# Schematic.net
KiCad netlist of a schematic drawn in EAGLE
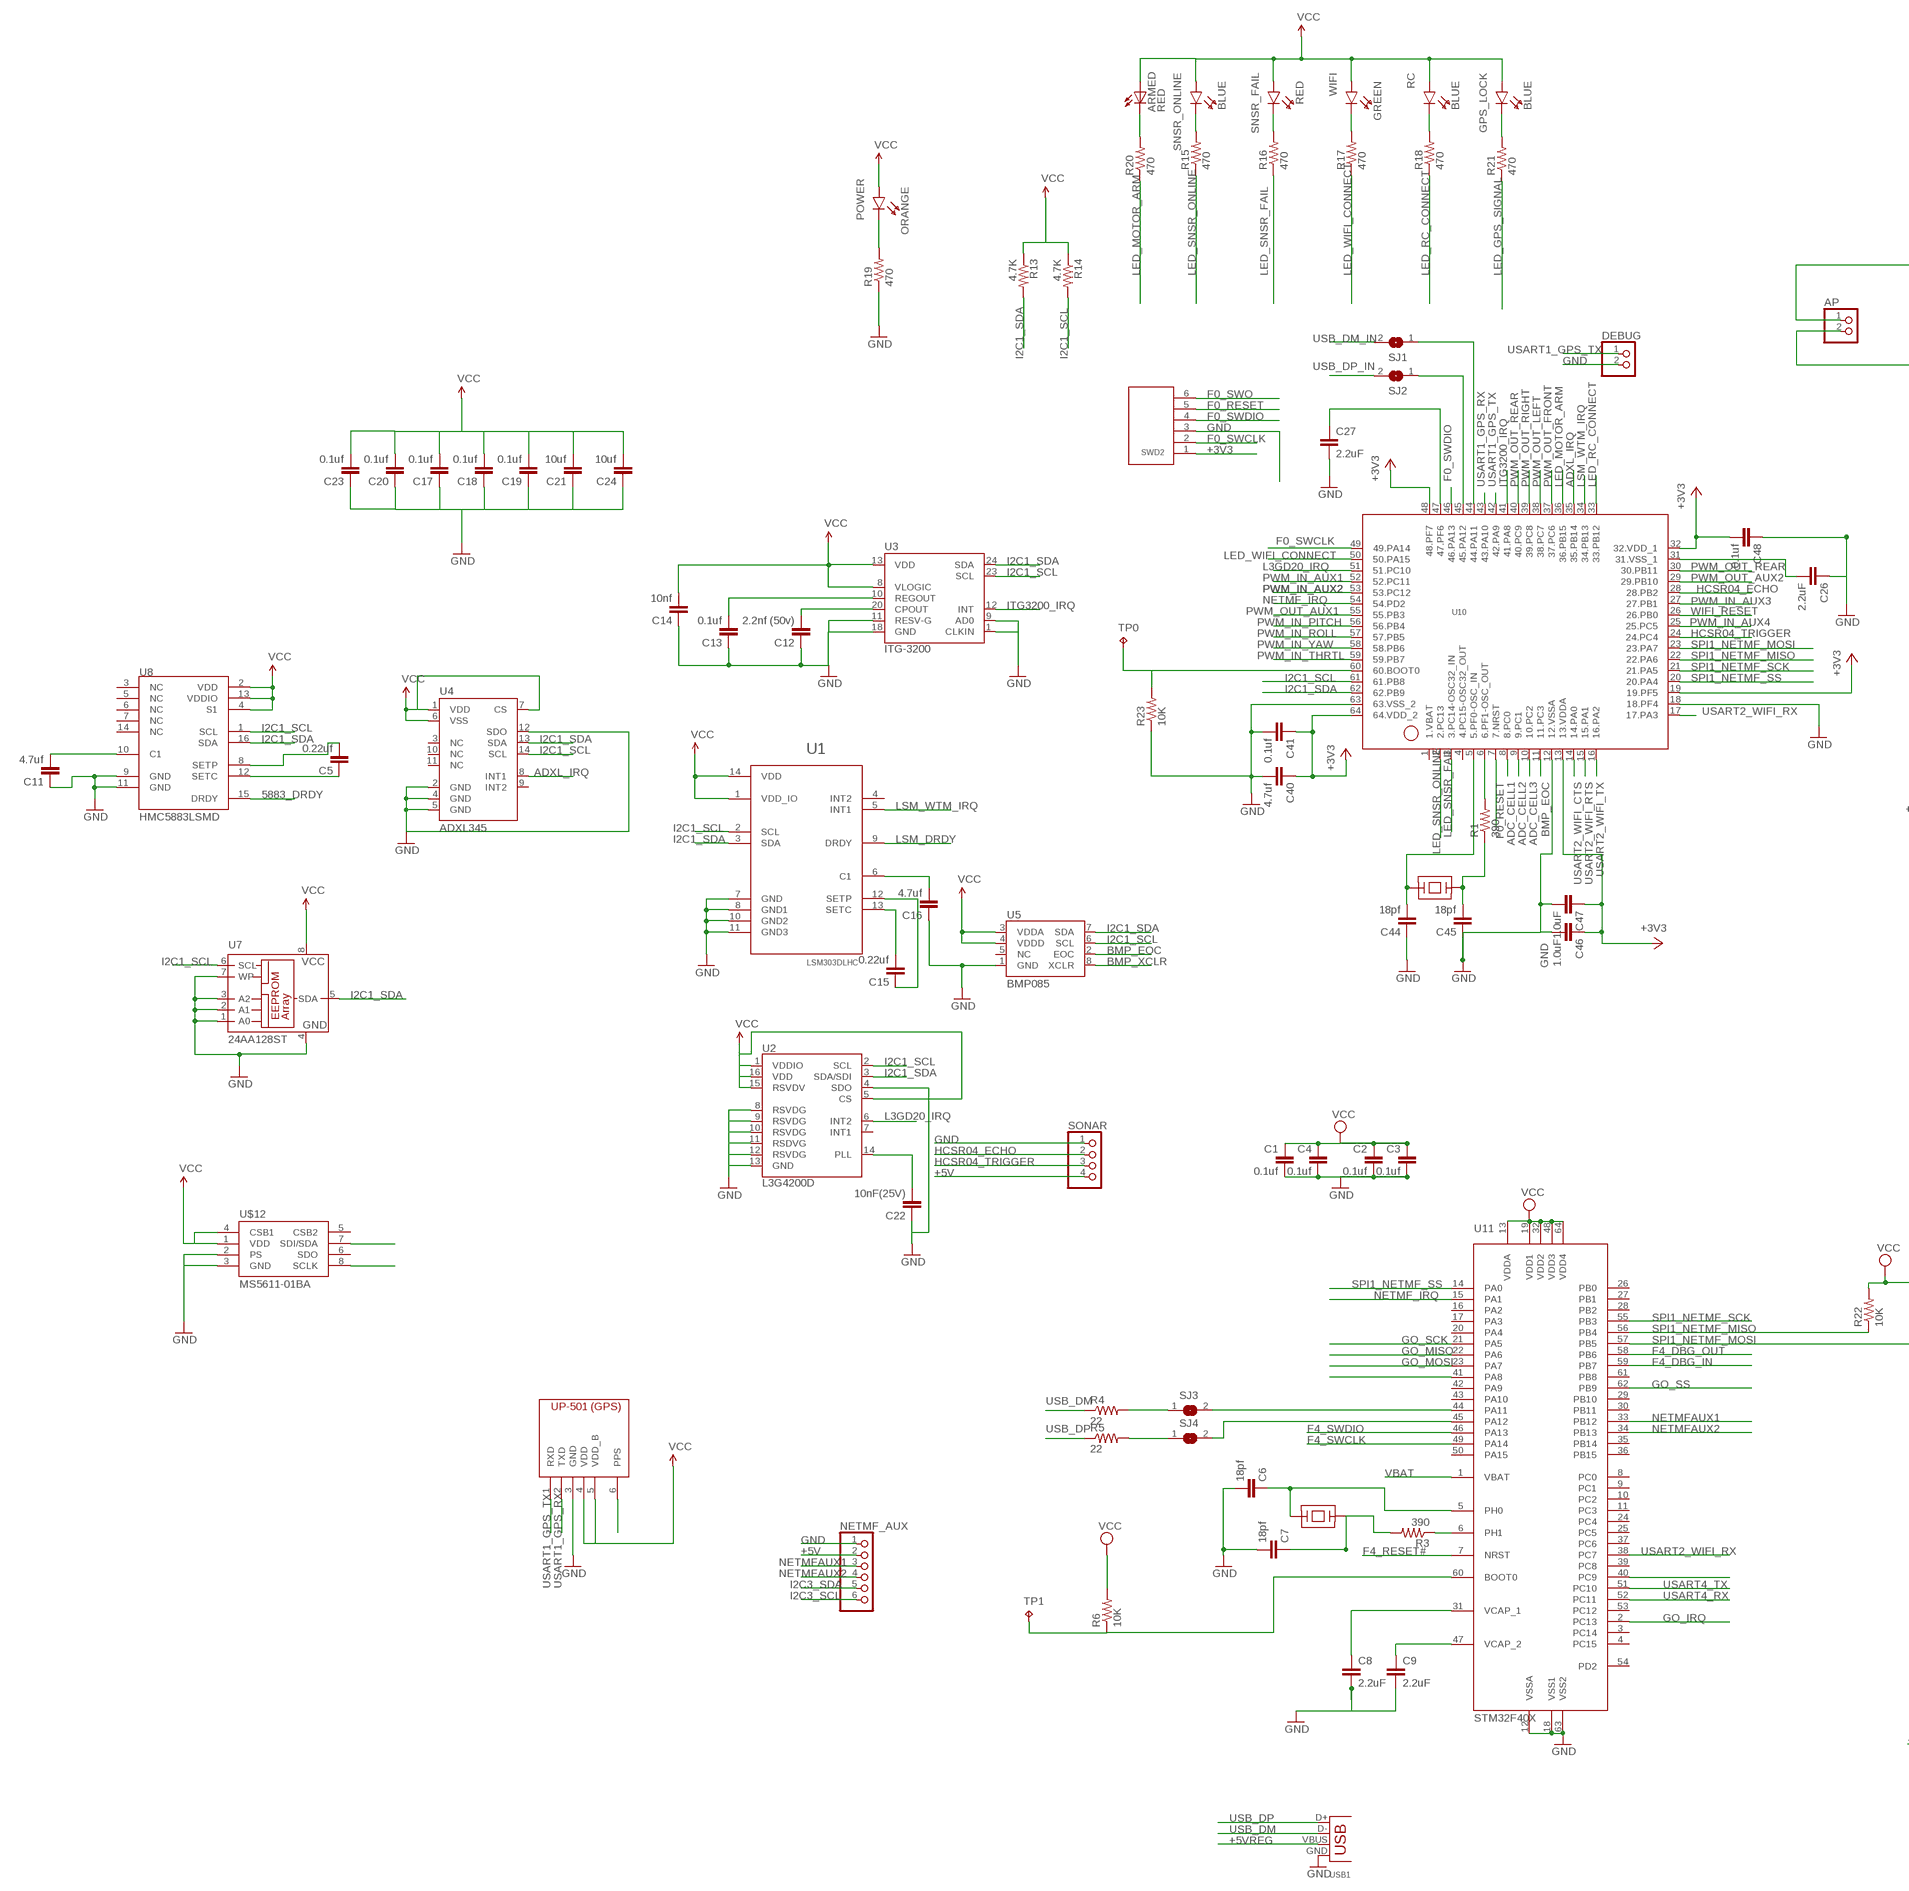
[diagram p0: schematic, sheet 1, part 1 of 2]
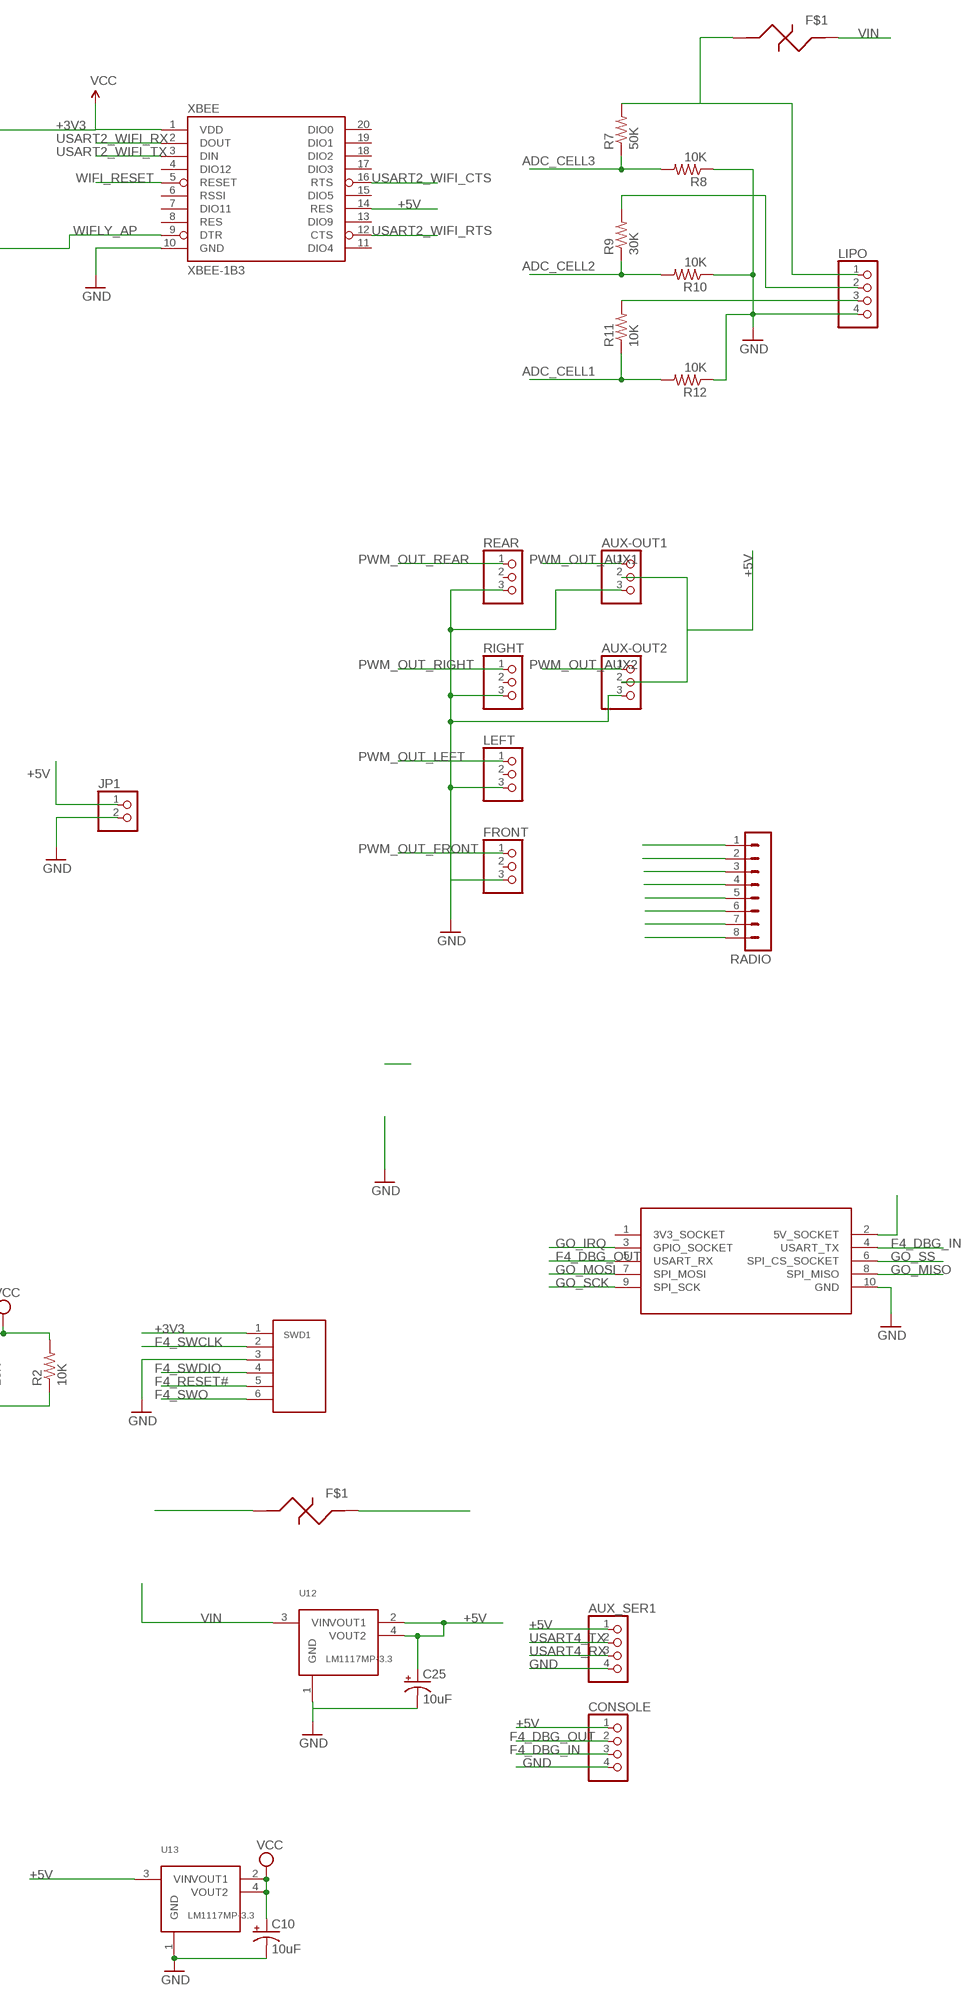
[diagram p1: schematic, sheet 1, part 2 of 2]

(export (version "E")
  (design (tool "Eeschema 10.0.6"))
  (components
    (comp (ref "AP")
      (value "PINHD-1X2")
      (footprint "eagle-import:1X02")
      (libsource (lib "eagle-import") (part "PINHD-1X2"))
    )
    (comp (ref "ARMED")
      (value "RED")
      (footprint "eagle-import:LED-1206")
      (libsource (lib "eagle-import") (part "LED-REDLILYPAD"))
    )
    (comp (ref "AUX-OUT1")
      (value "PINHD-1X3")
      (footprint "eagle-import:1X03")
      (libsource (lib "eagle-import") (part "PINHD-1X3"))
    )
    (comp (ref "AUX-OUT2")
      (value "PINHD-1X3")
      (footprint "eagle-import:1X03")
      (libsource (lib "eagle-import") (part "PINHD-1X3"))
    )
    (comp (ref "AUX_SER1")
      (value "PINHD-1X4")
      (footprint "eagle-import:1X04")
      (libsource (lib "eagle-import") (part "PINHD-1X4"))
    )
    (comp (ref "C1")
      (value "0.1uf")
      (footprint "eagle-import:0805")
      (libsource (lib "eagle-import") (part "SparkFun-Passives_CAP0805"))
    )
    (comp (ref "C2")
      (value "0.1uf")
      (footprint "eagle-import:0805")
      (libsource (lib "eagle-import") (part "SparkFun-Passives_CAP0805"))
    )
    (comp (ref "C3")
      (value "0.1uf")
      (footprint "eagle-import:0805")
      (libsource (lib "eagle-import") (part "SparkFun-Passives_CAP0805"))
    )
    (comp (ref "C4")
      (value "0.1uf")
      (footprint "eagle-import:0805")
      (libsource (lib "eagle-import") (part "SparkFun-Passives_CAP0805"))
    )
    (comp (ref "C5")
      (value "0.22uf")
      (footprint "eagle-import:0805")
      (libsource (lib "eagle-import") (part "CAP0805"))
    )
    (comp (ref "C6")
      (value "18pf")
      (footprint "eagle-import:0805")
      (libsource (lib "eagle-import") (part "SparkFun-Passives_CAP0805"))
    )
    (comp (ref "C7")
      (value "18pf")
      (footprint "eagle-import:0805")
      (libsource (lib "eagle-import") (part "SparkFun-Passives_CAP0805"))
    )
    (comp (ref "C8")
      (value "2.2uF")
      (footprint "eagle-import:0805")
      (libsource (lib "eagle-import") (part "SparkFun-Passives_CAP0805"))
    )
    (comp (ref "C9")
      (value "2.2uF")
      (footprint "eagle-import:0805")
      (libsource (lib "eagle-import") (part "SparkFun-Passives_CAP0805"))
    )
    (comp (ref "C10")
      (value "10uF")
      (footprint "eagle-import:CT3528")
      (libsource (lib "eagle-import") (part "CPOL-USCT3528"))
    )
    (comp (ref "C11")
      (value "4.7uf")
      (footprint "eagle-import:0805")
      (libsource (lib "eagle-import") (part "CAP0805"))
    )
    (comp (ref "C12")
      (value "2.2nf (50v)")
      (footprint "eagle-import:0805")
      (libsource (lib "eagle-import") (part "CAP0805"))
    )
    (comp (ref "C13")
      (value "0.1uf")
      (footprint "eagle-import:0805")
      (libsource (lib "eagle-import") (part "CAP0805"))
    )
    (comp (ref "C14")
      (value "10nf")
      (footprint "eagle-import:0805")
      (libsource (lib "eagle-import") (part "CAP0805"))
    )
    (comp (ref "C15")
      (value "0.22uf")
      (footprint "eagle-import:0805")
      (libsource (lib "eagle-import") (part "CAP0805"))
    )
    (comp (ref "C16")
      (value "4.7uf")
      (footprint "eagle-import:0805")
      (libsource (lib "eagle-import") (part "CAP0805"))
    )
    (comp (ref "C17")
      (value "0.1uf")
      (footprint "eagle-import:0805")
      (libsource (lib "eagle-import") (part "CAP0805"))
    )
    (comp (ref "C18")
      (value "0.1uf")
      (footprint "eagle-import:0805")
      (libsource (lib "eagle-import") (part "CAP0805"))
    )
    (comp (ref "C19")
      (value "0.1uf")
      (footprint "eagle-import:0805")
      (libsource (lib "eagle-import") (part "CAP0805"))
    )
    (comp (ref "C20")
      (value "0.1uf")
      (footprint "eagle-import:0805")
      (libsource (lib "eagle-import") (part "CAP0805"))
    )
    (comp (ref "C21")
      (value "10uf")
      (footprint "eagle-import:0805")
      (libsource (lib "eagle-import") (part "CAP0805"))
    )
    (comp (ref "C22")
      (value "10nF(25V)")
      (footprint "eagle-import:0805")
      (libsource (lib "eagle-import") (part "CAP0805"))
    )
    (comp (ref "C23")
      (value "0.1uf")
      (footprint "eagle-import:0805")
      (libsource (lib "eagle-import") (part "CAP0805"))
    )
    (comp (ref "C24")
      (value "10uf")
      (footprint "eagle-import:0805")
      (libsource (lib "eagle-import") (part "CAP0805"))
    )
    (comp (ref "C25")
      (value "10uF")
      (footprint "eagle-import:CT3528")
      (libsource (lib "eagle-import") (part "CPOL-USCT3528"))
    )
    (comp (ref "C26")
      (value "2.2uF")
      (footprint "eagle-import:0805")
      (libsource (lib "eagle-import") (part "SparkFun-Passives_CAP0805"))
    )
    (comp (ref "C27")
      (value "2.2uF")
      (footprint "eagle-import:0805")
      (libsource (lib "eagle-import") (part "SparkFun-Passives_CAP0805"))
    )
    (comp (ref "C40")
      (value "4.7uf")
      (footprint "eagle-import:0805")
      (libsource (lib "eagle-import") (part "SparkFun-Passives_CAP0805"))
    )
    (comp (ref "C41")
      (value "0.1uf")
      (footprint "eagle-import:0805")
      (libsource (lib "eagle-import") (part "SparkFun-Passives_CAP0805"))
    )
    (comp (ref "C44")
      (value "18pf")
      (footprint "eagle-import:0805")
      (libsource (lib "eagle-import") (part "SparkFun-Passives_CAP0805"))
    )
    (comp (ref "C45")
      (value "18pf")
      (footprint "eagle-import:0805")
      (libsource (lib "eagle-import") (part "SparkFun-Passives_CAP0805"))
    )
    (comp (ref "C46")
      (value "1.0uF")
      (footprint "eagle-import:0805")
      (libsource (lib "eagle-import") (part "SparkFun-Passives_CAP0805"))
    )
    (comp (ref "C47")
      (value "1.0uF")
      (footprint "eagle-import:0805")
      (libsource (lib "eagle-import") (part "SparkFun-Passives_CAP0805"))
    )
    (comp (ref "C48")
      (value "0.1uf")
      (footprint "eagle-import:0805")
      (libsource (lib "eagle-import") (part "SparkFun-Passives_CAP0805"))
    )
    (comp (ref "CONSOLE")
      (value "PINHD-1X4")
      (footprint "eagle-import:1X04")
      (libsource (lib "eagle-import") (part "PINHD-1X4"))
    )
    (comp (ref "DEBUG")
      (value "PINHD-1X2")
      (footprint "eagle-import:1X02")
      (libsource (lib "eagle-import") (part "PINHD-1X2"))
    )
    (comp (ref "F1")
      (value "1206L050_FUSE")
      (footprint "eagle-import:1206L050_FUSE")
      (libsource (lib "eagle-import") (part "1206L050_FUSE"))
    )
    (comp (ref "F2")
      (value "1206L050_FUSE")
      (footprint "eagle-import:1206L050_FUSE")
      (libsource (lib "eagle-import") (part "1206L050_FUSE"))
    )
    (comp (ref "FRONT")
      (value "PINHD-1X3")
      (footprint "eagle-import:1X03")
      (libsource (lib "eagle-import") (part "PINHD-1X3"))
    )
    (comp (ref "GO_BUS")
      (value "GO!BUS")
      (footprint "eagle-import:PIN2ROW_0.05_")
      (libsource (lib "eagle-import") (part "GO!BUS"))
    )
    (comp (ref "GPS_LOCK")
      (value "BLUE")
      (footprint "eagle-import:LED0805")
      (libsource (lib "eagle-import") (part "SMD_LED0805"))
    )
    (comp (ref "JP1")
      (value "PINHD-1X2")
      (footprint "eagle-import:1X02")
      (libsource (lib "eagle-import") (part "PINHD-1X2"))
    )
    (comp (ref "LEFT")
      (value "PINHD-1X3")
      (footprint "eagle-import:1X03")
      (libsource (lib "eagle-import") (part "PINHD-1X3"))
    )
    (comp (ref "LIPO")
      (value "PINHD-1X4")
      (footprint "eagle-import:1X04")
      (libsource (lib "eagle-import") (part "PINHD-1X4"))
    )
    (comp (ref "NETMF_AUX")
      (value "PINHD-1X6")
      (footprint "eagle-import:1X06")
      (libsource (lib "eagle-import") (part "PINHD-1X6"))
    )
    (comp (ref "POWER")
      (value "ORANGE")
      (footprint "eagle-import:LED0805")
      (libsource (lib "eagle-import") (part "SMD_LED0805"))
    )
    (comp (ref "R1")
      (value "390")
      (footprint "eagle-import:0805")
      (libsource (lib "eagle-import") (part "RESISTOR0805-RES"))
    )
    (comp (ref "R2")
      (value "10K")
      (footprint "eagle-import:0805")
      (libsource (lib "eagle-import") (part "RESISTOR0805-RES"))
    )
    (comp (ref "R3")
      (value "390")
      (footprint "eagle-import:0805")
      (libsource (lib "eagle-import") (part "RESISTOR0805-RES"))
    )
    (comp (ref "R4")
      (value "22")
      (footprint "eagle-import:0805")
      (libsource (lib "eagle-import") (part "RESISTOR0805-RES"))
    )
    (comp (ref "R5")
      (value "22")
      (footprint "eagle-import:0805")
      (libsource (lib "eagle-import") (part "RESISTOR0805-RES"))
    )
    (comp (ref "R6")
      (value "10K")
      (footprint "eagle-import:0805")
      (libsource (lib "eagle-import") (part "RESISTOR0805-RES"))
    )
    (comp (ref "R7")
      (value "50K")
      (footprint "eagle-import:0805")
      (libsource (lib "eagle-import") (part "RESISTOR0805-RES"))
    )
    (comp (ref "R8")
      (value "10K")
      (footprint "eagle-import:0805")
      (libsource (lib "eagle-import") (part "RESISTOR0805-RES"))
    )
    (comp (ref "R9")
      (value "30K")
      (footprint "eagle-import:0805")
      (libsource (lib "eagle-import") (part "RESISTOR0805-RES"))
    )
    (comp (ref "R10")
      (value "10K")
      (footprint "eagle-import:0805")
      (libsource (lib "eagle-import") (part "RESISTOR0805-RES"))
    )
    (comp (ref "R11")
      (value "10K")
      (footprint "eagle-import:0805")
      (libsource (lib "eagle-import") (part "RESISTOR0805-RES"))
    )
    (comp (ref "R12")
      (value "10K")
      (footprint "eagle-import:0805")
      (libsource (lib "eagle-import") (part "RESISTOR0805-RES"))
    )
    (comp (ref "R13")
      (value "4.7K")
      (footprint "eagle-import:0805")
      (libsource (lib "eagle-import") (part "RESISTOR0805-RES"))
    )
    (comp (ref "R14")
      (value "4.7K")
      (footprint "eagle-import:0805")
      (libsource (lib "eagle-import") (part "RESISTOR0805-RES"))
    )
    (comp (ref "R15")
      (value "470")
      (footprint "eagle-import:0805")
      (libsource (lib "eagle-import") (part "RESISTOR0805-RES"))
    )
    (comp (ref "R16")
      (value "470")
      (footprint "eagle-import:0805")
      (libsource (lib "eagle-import") (part "RESISTOR0805-RES"))
    )
    (comp (ref "R17")
      (value "470")
      (footprint "eagle-import:0805")
      (libsource (lib "eagle-import") (part "RESISTOR0805-RES"))
    )
    (comp (ref "R18")
      (value "470")
      (footprint "eagle-import:0805")
      (libsource (lib "eagle-import") (part "RESISTOR0805-RES"))
    )
    (comp (ref "R19")
      (value "470")
      (footprint "eagle-import:0805")
      (libsource (lib "eagle-import") (part "RESISTOR0805-RES"))
    )
    (comp (ref "R20")
      (value "470")
      (footprint "eagle-import:0805")
      (libsource (lib "eagle-import") (part "RESISTOR0805-RES"))
    )
    (comp (ref "R21")
      (value "470")
      (footprint "eagle-import:0805")
      (libsource (lib "eagle-import") (part "RESISTOR0805-RES"))
    )
    (comp (ref "R22")
      (value "10K")
      (footprint "eagle-import:0805")
      (libsource (lib "eagle-import") (part "RESISTOR0805-RES"))
    )
    (comp (ref "R23")
      (value "10K")
      (footprint "eagle-import:0805")
      (libsource (lib "eagle-import") (part "RESISTOR0805-RES"))
    )
    (comp (ref "RADIO")
      (value "MA08-1")
      (footprint "eagle-import:MA08-1")
      (libsource (lib "eagle-import") (part "MA08-1"))
    )
    (comp (ref "RC")
      (value "BLUE")
      (footprint "eagle-import:LED0805")
      (libsource (lib "eagle-import") (part "SMD_LED0805"))
    )
    (comp (ref "REAR")
      (value "PINHD-1X3")
      (footprint "eagle-import:1X03")
      (libsource (lib "eagle-import") (part "PINHD-1X3"))
    )
    (comp (ref "RIGHT")
      (value "PINHD-1X3")
      (footprint "eagle-import:1X03")
      (libsource (lib "eagle-import") (part "PINHD-1X3"))
    )
    (comp (ref "SJ1") (value "SJ") (footprint "eagle-import:SJ") (libsource (lib "eagle-import") (part "SJ")))
    (comp (ref "SJ2") (value "SJ") (footprint "eagle-import:SJ") (libsource (lib "eagle-import") (part "SJ")))
    (comp (ref "SJ3") (value "SJ") (footprint "eagle-import:SJ") (libsource (lib "eagle-import") (part "SJ")))
    (comp (ref "SJ4") (value "SJ") (footprint "eagle-import:SJ") (libsource (lib "eagle-import") (part "SJ")))
    (comp (ref "SNSR_FAIL")
      (value "RED")
      (footprint "eagle-import:LED0805")
      (libsource (lib "eagle-import") (part "SMD_LED0805"))
    )
    (comp (ref "SNSR_ONLINE")
      (value "BLUE")
      (footprint "eagle-import:LED0805")
      (libsource (lib "eagle-import") (part "SMD_LED0805"))
    )
    (comp (ref "SONAR")
      (value "PINHD-1X4")
      (footprint "eagle-import:1X04")
      (libsource (lib "eagle-import") (part "PINHD-1X4"))
    )
    (comp (ref "SWD1")
      (value "JST-6PIN")
      (footprint "eagle-import:JSTX6")
      (libsource (lib "eagle-import") (part "JST-6PIN"))
    )
    (comp (ref "SWD2")
      (value "SWD-STM32F0")
      (footprint "eagle-import:JSTX6")
      (libsource (lib "eagle-import") (part "JST-6PIN"))
    )
    (comp (ref "TP0")
      (value "TPTP15R")
      (footprint "eagle-import:TP15R")
      (libsource (lib "eagle-import") (part "TPTP15R"))
    )
    (comp (ref "TP1")
      (value "TPTP15R")
      (footprint "eagle-import:TP15R")
      (libsource (lib "eagle-import") (part "TPTP15R"))
    )
    (comp (ref "U$4")
      (value "UP501")
      (footprint "eagle-import:UP-501")
      (libsource (lib "eagle-import") (part "UP501"))
    )
    (comp (ref "U$12")
      (value "MS5611-01BA")
      (footprint "eagle-import:MS5611-01BA")
      (libsource (lib "eagle-import") (part "MS5611-01BA"))
    )
    (comp (ref "U1")
      (value "LSM303DLHC")
      (footprint "eagle-import:LGA3X5X1-14L")
      (libsource (lib "eagle-import") (part "LSM303DLHC"))
    )
    (comp (ref "U2")
      (value "L3G4200D")
      (footprint "eagle-import:LGA16-4X4")
      (libsource (lib "eagle-import") (part "L3G4200D"))
    )
    (comp (ref "U3")
      (value "ITG-3200")
      (footprint "eagle-import:QFN-24")
      (libsource (lib "eagle-import") (part "ITG-3200"))
    )
    (comp (ref "U4")
      (value "ADXL345")
      (footprint "eagle-import:LGA14")
      (libsource (lib "eagle-import") (part "ADXL345"))
    )
    (comp (ref "U5")
      (value "BMP085")
      (footprint "eagle-import:BMP085")
      (libsource (lib "eagle-import") (part "BMP085"))
    )
    (comp (ref "U7")
      (value "24AA128ST")
      (footprint "eagle-import:TSSOP8")
      (fields
        (field (name "MF") "MICROCHIP")
        (field (name "MPN") "24AA128-I/ST")
        (field (name "MPN_1") "24AA128-I/ST")
        (field (name "OC_FARNELL") "unknown")
        (field (name "OC_NEWARK") "92C6843")
      )
      (libsource (lib "eagle-import") (part "24STAA128"))
    )
    (comp (ref "U8")
      (value "HMC5883LSMD")
      (footprint "eagle-import:16LPCC")
      (libsource (lib "eagle-import") (part "HMC5883LSMD"))
    )
    (comp (ref "U10")
      (value "STM32F051XXX")
      (footprint "eagle-import:STM32F051XXX_LPFP64")
      (libsource (lib "eagle-import") (part "STM32F051XXX"))
    )
    (comp (ref "U11")
      (value "STM32F40X")
      (footprint "eagle-import:LQFP64")
      (libsource (lib "eagle-import") (part "STM32F40X"))
    )
    (comp (ref "U12")
      (value "LM1117MP-3.3")
      (footprint "eagle-import:SOT223")
      (libsource (lib "eagle-import") (part "LM1117"))
    )
    (comp (ref "U13")
      (value "LM1117MP-3.3")
      (footprint "eagle-import:SOT223")
      (libsource (lib "eagle-import") (part "LM1117"))
    )
    (comp (ref "USB1")
      (value "DX2R005HN2E700")
      (footprint "eagle-import:USB-MB-S")
      (libsource (lib "eagle-import") (part "USB-MB-S"))
    )
    (comp (ref "WIFI")
      (value "GREEN")
      (footprint "eagle-import:LED0805")
      (libsource (lib "eagle-import") (part "SMD_LED0805"))
    )
    (comp (ref "X1")
      (value "ABRACON_ABM7")
      (footprint "eagle-import:ABRACON_ABM7_CERAMIC_XTAL")
      (libsource (lib "eagle-import") (part "ABRACON_ABM7"))
    )
    (comp (ref "X2")
      (value "ABRACON_ABM7")
      (footprint "eagle-import:ABRACON_ABM7_CERAMIC_XTAL")
      (libsource (lib "eagle-import") (part "ABRACON_ABM7"))
    )
    (comp (ref "XBEE")
      (value "XBEE-1B3")
      (footprint "eagle-import:XBEE-SMD")
      (libsource (lib "eagle-import") (part "XBEE-1B3"))
    )
  )
  (nets
    (net (code "1") (name "+3V3") (class "Default")
      (node (ref "AP") (pin "1") (pinfunction "1_1") (pintype "passive"))
      (node (ref "ARMED") (pin "A") (pinfunction "A_A") (pintype "passive"))
      (node (ref "C1") (pin "1") (pinfunction "1_1") (pintype "passive"))
      (node (ref "C10") (pin "+") (pinfunction "+_+") (pintype "passive"))
      (node (ref "C14") (pin "2") (pinfunction "2_2") (pintype "passive"))
      (node (ref "C17") (pin "2") (pinfunction "2_2") (pintype "passive"))
      (node (ref "C18") (pin "2") (pinfunction "2_2") (pintype "passive"))
      (node (ref "C19") (pin "2") (pinfunction "2_2") (pintype "passive"))
      (node (ref "C2") (pin "1") (pinfunction "1_1") (pintype "passive"))
      (node (ref "C20") (pin "2") (pinfunction "2_2") (pintype "passive"))
      (node (ref "C21") (pin "2") (pinfunction "2_2") (pintype "passive"))
      (node (ref "C23") (pin "2") (pinfunction "2_2") (pintype "passive"))
      (node (ref "C24") (pin "2") (pinfunction "2_2") (pintype "passive"))
      (node (ref "C3") (pin "1") (pinfunction "1_1") (pintype "passive"))
      (node (ref "C4") (pin "1") (pinfunction "1_1") (pintype "passive"))
      (node (ref "C40") (pin "1") (pinfunction "1_1") (pintype "passive"))
      (node (ref "C41") (pin "1") (pinfunction "1_1") (pintype "passive"))
      (node (ref "C46") (pin "1") (pinfunction "1_1") (pintype "passive"))
      (node (ref "C47") (pin "1") (pinfunction "1_1") (pintype "passive"))
      (node (ref "C48") (pin "2") (pinfunction "2_2") (pintype "passive"))
      (node (ref "GPS_LOCK") (pin "P$1") (pinfunction "A_P$1") (pintype "passive"))
      (node (ref "POWER") (pin "P$1") (pinfunction "A_P$1") (pintype "passive"))
      (node (ref "R13") (pin "1") (pinfunction "1_1") (pintype "passive"))
      (node (ref "R14") (pin "1") (pinfunction "1_1") (pintype "passive"))
      (node (ref "R2") (pin "2") (pinfunction "2_2") (pintype "passive"))
      (node (ref "R22") (pin "2") (pinfunction "2_2") (pintype "passive"))
      (node (ref "R6") (pin "2") (pinfunction "2_2") (pintype "passive"))
      (node (ref "RC") (pin "P$1") (pinfunction "A_P$1") (pintype "passive"))
      (node (ref "SNSR_FAIL") (pin "P$1") (pinfunction "A_P$1") (pintype "passive"))
      (node (ref "SNSR_ONLINE") (pin "P$1") (pinfunction "A_P$1") (pintype "passive"))
      (node (ref "SWD1") (pin "1") (pinfunction "P$1_1") (pintype "bidirectional"))
      (node (ref "SWD2") (pin "1") (pinfunction "P$1_1") (pintype "bidirectional"))
      (node (ref "U$12") (pin "1") (pinfunction "VDD_1") (pintype "bidirectional"))
      (node (ref "U$12") (pin "4") (pinfunction "CSB1_4") (pintype "bidirectional"))
      (node (ref "U$4") (pin "4") (pinfunction "VDD_4") (pintype "bidirectional"))
      (node (ref "U$4") (pin "5") (pinfunction "VDD_B_5") (pintype "bidirectional"))
      (node (ref "U1") (pin "1") (pinfunction "VDD_IO_1") (pintype "power_in"))
      (node (ref "U1") (pin "14") (pinfunction "VDD_14") (pintype "power_in"))
      (node (ref "U10") (pin "13") (pinfunction "13.VDDA_13") (pintype "power_in"))
      (node (ref "U10") (pin "19") (pinfunction "19.PF5_19") (pintype "bidirectional"))
      (node (ref "U10") (pin "32") (pinfunction "32.VDD_1_32") (pintype "power_in"))
      (node (ref "U10") (pin "48") (pinfunction "48.PF7_48") (pintype "power_in"))
      (node (ref "U10") (pin "64") (pinfunction "64.VDD_2_64") (pintype "power_in"))
      (node (ref "U11") (pin "13") (pinfunction "VDDA_13") (pintype "bidirectional"))
      (node (ref "U11") (pin "19") (pinfunction "VDD1_19") (pintype "bidirectional"))
      (node (ref "U11") (pin "32") (pinfunction "VDD2_32") (pintype "bidirectional"))
      (node (ref "U11") (pin "48") (pinfunction "VDD3_48") (pintype "bidirectional"))
      (node (ref "U11") (pin "64") (pinfunction "VDD4_64") (pintype "bidirectional"))
      (node (ref "U13") (pin "2") (pinfunction "VOUT1_2") (pintype "bidirectional"))
      (node (ref "U13") (pin "4") (pinfunction "VOUT2_4") (pintype "bidirectional"))
      (node (ref "U2") (pin "1") (pinfunction "VDDIO_1") (pintype "bidirectional"))
      (node (ref "U2") (pin "15") (pinfunction "RSVDV_15") (pintype "bidirectional"))
      (node (ref "U2") (pin "16") (pinfunction "VDD_16") (pintype "bidirectional"))
      (node (ref "U2") (pin "5") (pinfunction "CS_5") (pintype "bidirectional"))
      (node (ref "U3") (pin "13") (pinfunction "VDD_13") (pintype "bidirectional"))
      (node (ref "U3") (pin "8") (pinfunction "VLOGIC_8") (pintype "bidirectional"))
      (node (ref "U4") (pin "1") (pinfunction "VDD_1") (pintype "bidirectional"))
      (node (ref "U4") (pin "6") (pinfunction "VSS_6") (pintype "bidirectional"))
      (node (ref "U4") (pin "7") (pinfunction "CS_7") (pintype "bidirectional"))
      (node (ref "U5") (pin "3") (pinfunction "VDDA_3") (pintype "power_in"))
      (node (ref "U5") (pin "4") (pinfunction "VDDD_4") (pintype "power_in"))
      (node (ref "U7") (pin "8") (pinfunction "VCC_8") (pintype "power_in"))
      (node (ref "U8") (pin "13") (pinfunction "VDDIO_13") (pintype "bidirectional"))
      (node (ref "U8") (pin "2") (pinfunction "VDD_2") (pintype "bidirectional"))
      (node (ref "U8") (pin "4") (pinfunction "S1_4") (pintype "bidirectional"))
      (node (ref "WIFI") (pin "P$1") (pinfunction "A_P$1") (pintype "passive"))
      (node (ref "XBEE") (pin "1") (pinfunction "VDD_1") (pintype "power_in"))
    )
    (net (code "2") (name "/+5V") (class "Default")
      (node (ref "AUX-OUT1") (pin "2") (pinfunction "2_2") (pintype "passive"))
      (node (ref "AUX-OUT2") (pin "2") (pinfunction "2_2") (pintype "passive"))
      (node (ref "AUX_SER1") (pin "1") (pinfunction "1_1") (pintype "passive"))
      (node (ref "C25") (pin "+") (pinfunction "+_+") (pintype "passive"))
      (node (ref "CONSOLE") (pin "1") (pinfunction "1_1") (pintype "passive"))
      (node (ref "F1") (pin "P$2") (pinfunction "P$2_P$2") (pintype "bidirectional"))
      (node (ref "GO_BUS") (pin "2") (pinfunction "5V_SOCKET_2") (pintype "power_in"))
      (node (ref "JP1") (pin "1") (pinfunction "1_1") (pintype "passive"))
      (node (ref "NETMF_AUX") (pin "2") (pinfunction "2_2") (pintype "passive"))
      (node (ref "SONAR") (pin "4") (pinfunction "4_4") (pintype "passive"))
      (node (ref "U12") (pin "2") (pinfunction "VOUT1_2") (pintype "bidirectional"))
      (node (ref "U12") (pin "4") (pinfunction "VOUT2_4") (pintype "bidirectional"))
      (node (ref "U13") (pin "3") (pinfunction "VIN_3") (pintype "bidirectional"))
      (node (ref "XBEE") (pin "14") (pinfunction "RES_14") (pintype "bidirectional"))
    )
    (net (code "3") (name "/+5VREG") (class "Default")
      (node (ref "F1") (pin "P$1") (pinfunction "P$1_P$1") (pintype "bidirectional"))
      (node (ref "USB1") (pin "VBUS") (pinfunction "VBUS_VBUS") (pintype "bidirectional"))
    )
    (net (code "4") (name "/1.VBAT") (class "Default")
      (node (ref "U10") (pin "1") (pinfunction "1.VBAT_1") (pintype "power_in"))
    )
    (net (code "5") (name "/3V3_SOCKET") (class "Default")
      (node (ref "GO_BUS") (pin "1") (pinfunction "3V3_SOCKET_1") (pintype "power_in"))
    )
    (net (code "6") (name "/5883_DRDY") (class "Default")
      (node (ref "U8") (pin "15") (pinfunction "DRDY_15") (pintype "bidirectional"))
    )
    (net (code "7") (name "/ADC_CELL1") (class "Default")
      (node (ref "R11") (pin "1") (pinfunction "1_1") (pintype "passive"))
      (node (ref "R12") (pin "2") (pinfunction "2_2") (pintype "passive"))
      (node (ref "U10") (pin "8") (pinfunction "8.PC0_8") (pintype "bidirectional"))
    )
    (net (code "8") (name "/ADC_CELL2") (class "Default")
      (node (ref "R10") (pin "2") (pinfunction "2_2") (pintype "passive"))
      (node (ref "R9") (pin "1") (pinfunction "1_1") (pintype "passive"))
      (node (ref "U10") (pin "9") (pinfunction "9.PC1_9") (pintype "bidirectional"))
    )
    (net (code "9") (name "/ADC_CELL3") (class "Default")
      (node (ref "R7") (pin "1") (pinfunction "1_1") (pintype "passive"))
      (node (ref "R8") (pin "2") (pinfunction "2_2") (pintype "passive"))
      (node (ref "U10") (pin "10") (pinfunction "10.PC2_10") (pintype "bidirectional"))
    )
    (net (code "10") (name "/ADXL_IRQ") (class "Default")
      (node (ref "U10") (pin "35") (pinfunction "35.PB14_35") (pintype "bidirectional"))
      (node (ref "U4") (pin "8") (pinfunction "INT1_8") (pintype "bidirectional"))
    )
    (net (code "11") (name "/BMP_EOC") (class "Default")
      (node (ref "U10") (pin "11") (pinfunction "11.PC3_11") (pintype "bidirectional"))
      (node (ref "U5") (pin "2") (pinfunction "EOC_2") (pintype "output"))
    )
    (net (code "12") (name "/BMP_XCLR") (class "Default")
      (node (ref "U5") (pin "8") (pinfunction "XCLR_8") (pintype "input"))
    )
    (net (code "13") (name "/F0_RESET") (class "Default")
      (node (ref "SWD2") (pin "5") (pinfunction "P$5_5") (pintype "bidirectional"))
      (node (ref "U10") (pin "7") (pinfunction "7.NRST_7") (pintype "bidirectional"))
    )
    (net (code "14") (name "/F0_SWCLK") (class "Default")
      (node (ref "SWD2") (pin "2") (pinfunction "P$2_2") (pintype "bidirectional"))
      (node (ref "U10") (pin "49") (pinfunction "49.PA14_49") (pintype "bidirectional"))
    )
    (net (code "15") (name "/F0_SWDIO") (class "Default")
      (node (ref "SWD2") (pin "4") (pinfunction "P$4_4") (pintype "bidirectional"))
      (node (ref "U10") (pin "46") (pinfunction "46.PA13_46") (pintype "bidirectional"))
    )
    (net (code "16") (name "/F0_SWO") (class "Default")
      (node (ref "SWD2") (pin "6") (pinfunction "P$6_6") (pintype "bidirectional"))
    )
    (net (code "17") (name "/F4_DBG_IN") (class "Default")
      (node (ref "CONSOLE") (pin "3") (pinfunction "3_3") (pintype "passive"))
      (node (ref "GO_BUS") (pin "4") (pinfunction "USART_TX_4") (pintype "output"))
      (node (ref "U11") (pin "59") (pinfunction "PB7_59") (pintype "bidirectional"))
    )
    (net (code "18") (name "/F4_DBG_OUT") (class "Default")
      (node (ref "CONSOLE") (pin "2") (pinfunction "2_2") (pintype "passive"))
      (node (ref "GO_BUS") (pin "5") (pinfunction "USART_RX_5") (pintype "input"))
      (node (ref "U11") (pin "58") (pinfunction "PB6_58") (pintype "bidirectional"))
    )
    (net (code "19") (name "/F4_RESET#") (class "Default")
      (node (ref "SWD1") (pin "5") (pinfunction "P$5_5") (pintype "bidirectional"))
      (node (ref "U11") (pin "7") (pinfunction "NRST_7") (pintype "bidirectional"))
    )
    (net (code "20") (name "/F4_SWCLK") (class "Default")
      (node (ref "SWD1") (pin "2") (pinfunction "P$2_2") (pintype "bidirectional"))
      (node (ref "U11") (pin "49") (pinfunction "PA14_49") (pintype "bidirectional"))
    )
    (net (code "21") (name "/F4_SWDIO") (class "Default")
      (node (ref "SWD1") (pin "4") (pinfunction "P$4_4") (pintype "bidirectional"))
      (node (ref "U11") (pin "46") (pinfunction "PA13_46") (pintype "bidirectional"))
    )
    (net (code "22") (name "/F4_SWO") (class "Default")
      (node (ref "SWD1") (pin "6") (pinfunction "P$6_6") (pintype "bidirectional"))
    )
    (net (code "23") (name "/GO_IRQ") (class "Default")
      (node (ref "GO_BUS") (pin "3") (pinfunction "GPIO_SOCKET_3") (pintype "output"))
      (node (ref "U11") (pin "2") (pinfunction "PC13_2") (pintype "bidirectional"))
    )
    (net (code "24") (name "/GO_MISO") (class "Default")
      (node (ref "GO_BUS") (pin "8") (pinfunction "SPI_MISO_8") (pintype "output"))
      (node (ref "U11") (pin "22") (pinfunction "PA6_22") (pintype "bidirectional"))
    )
    (net (code "25") (name "/GO_MOSI") (class "Default")
      (node (ref "GO_BUS") (pin "7") (pinfunction "SPI_MOSI_7") (pintype "output"))
      (node (ref "U11") (pin "23") (pinfunction "PA7_23") (pintype "bidirectional"))
    )
    (net (code "26") (name "/GO_SCK") (class "Default")
      (node (ref "GO_BUS") (pin "9") (pinfunction "SPI_SCK_9") (pintype "output"))
      (node (ref "U11") (pin "21") (pinfunction "PA5_21") (pintype "bidirectional"))
    )
    (net (code "27") (name "/GO_SS") (class "Default")
      (node (ref "GO_BUS") (pin "6") (pinfunction "SPI_CS_SOCKET_6") (pintype "output"))
      (node (ref "U11") (pin "62") (pinfunction "PB9_62") (pintype "bidirectional"))
    )
    (net (code "28") (name "/HCSR04_ECHO") (class "Default")
      (node (ref "SONAR") (pin "2") (pinfunction "2_2") (pintype "passive"))
      (node (ref "U10") (pin "28") (pinfunction "28.PB2_28") (pintype "bidirectional"))
    )
    (net (code "29") (name "/HCSR04_TRIGGER") (class "Default")
      (node (ref "SONAR") (pin "3") (pinfunction "3_3") (pintype "passive"))
      (node (ref "U10") (pin "24") (pinfunction "24.PC4_24") (pintype "bidirectional"))
    )
    (net (code "30") (name "/I2C1_SCL") (class "Default")
      (node (ref "R14") (pin "2") (pinfunction "2_2") (pintype "passive"))
      (node (ref "U$12") (pin "8") (pinfunction "SCLK_8") (pintype "bidirectional"))
      (node (ref "U1") (pin "2") (pinfunction "SCL_2") (pintype "bidirectional"))
      (node (ref "U10") (pin "61") (pinfunction "61.PB8_61") (pintype "bidirectional"))
      (node (ref "U2") (pin "2") (pinfunction "SCL_2") (pintype "bidirectional"))
      (node (ref "U3") (pin "23") (pinfunction "SCL_23") (pintype "bidirectional"))
      (node (ref "U4") (pin "14") (pinfunction "SCL_14") (pintype "bidirectional"))
      (node (ref "U5") (pin "6") (pinfunction "SCL_6") (pintype "input"))
      (node (ref "U7") (pin "6") (pinfunction "SCL_6") (pintype "input"))
      (node (ref "U8") (pin "1") (pinfunction "SCL_1") (pintype "bidirectional"))
    )
    (net (code "31") (name "/I2C1_SDA") (class "Default")
      (node (ref "R13") (pin "2") (pinfunction "2_2") (pintype "passive"))
      (node (ref "U$12") (pin "7") (pinfunction "SDI/SDA_7") (pintype "bidirectional"))
      (node (ref "U1") (pin "3") (pinfunction "SDA_3") (pintype "bidirectional"))
      (node (ref "U10") (pin "62") (pinfunction "62.PB9_62") (pintype "bidirectional"))
      (node (ref "U2") (pin "3") (pinfunction "SDA/SDI_3") (pintype "bidirectional"))
      (node (ref "U3") (pin "24") (pinfunction "SDA_24") (pintype "bidirectional"))
      (node (ref "U4") (pin "13") (pinfunction "SDA_13") (pintype "bidirectional"))
      (node (ref "U5") (pin "7") (pinfunction "SDA_7") (pintype "bidirectional"))
      (node (ref "U7") (pin "5") (pinfunction "SDA_5") (pintype "bidirectional"))
      (node (ref "U8") (pin "16") (pinfunction "SDA_16") (pintype "bidirectional"))
    )
    (net (code "32") (name "/I2C3_SCL") (class "Default")
      (node (ref "NETMF_AUX") (pin "6") (pinfunction "6_6") (pintype "passive"))
      (node (ref "U11") (pin "41") (pinfunction "PA8_41") (pintype "bidirectional"))
    )
    (net (code "33") (name "/I2C3_SDA") (class "Default")
      (node (ref "NETMF_AUX") (pin "5") (pinfunction "5_5") (pintype "passive"))
      (node (ref "U11") (pin "40") (pinfunction "PC9_40") (pintype "bidirectional"))
    )
    (net (code "34") (name "/ITG3200_IRQ") (class "Default")
      (node (ref "U10") (pin "41") (pinfunction "41.PA8_41") (pintype "bidirectional"))
      (node (ref "U3") (pin "12") (pinfunction "INT_12") (pintype "bidirectional"))
    )
    (net (code "35") (name "/L3GD20_IRQ") (class "Default")
      (node (ref "U10") (pin "51") (pinfunction "51.PC10_51") (pintype "bidirectional"))
      (node (ref "U2") (pin "6") (pinfunction "INT2_6") (pintype "bidirectional"))
    )
    (net (code "36") (name "/LED_GPS_SIGNAL") (class "Default")
      (node (ref "R21") (pin "1") (pinfunction "1_1") (pintype "passive"))
      (node (ref "U$4") (pin "6") (pinfunction "PPS_6") (pintype "bidirectional"))
    )
    (net (code "37") (name "/LED_MOTOR_ARM") (class "Default")
      (node (ref "R20") (pin "1") (pinfunction "1_1") (pintype "passive"))
      (node (ref "U10") (pin "36") (pinfunction "36.PB15_36") (pintype "bidirectional"))
    )
    (net (code "38") (name "/LED_RC_CONNECT") (class "Default")
      (node (ref "R18") (pin "1") (pinfunction "1_1") (pintype "passive"))
      (node (ref "U10") (pin "33") (pinfunction "33.PB12_33") (pintype "bidirectional"))
    )
    (net (code "39") (name "/LED_SNSR_FAIL") (class "Default")
      (node (ref "R16") (pin "1") (pinfunction "1_1") (pintype "passive"))
      (node (ref "U10") (pin "3") (pinfunction "3.PC14-OSC32_IN_3") (pintype "bidirectional"))
    )
    (net (code "40") (name "/LED_SNSR_ONLINE") (class "Default")
      (node (ref "R15") (pin "1") (pinfunction "1_1") (pintype "passive"))
      (node (ref "U10") (pin "2") (pinfunction "2.PC13_2") (pintype "bidirectional"))
    )
    (net (code "41") (name "/LED_WIFI_CONNECT") (class "Default")
      (node (ref "R17") (pin "1") (pinfunction "1_1") (pintype "passive"))
      (node (ref "U10") (pin "50") (pinfunction "50.PA15_50") (pintype "bidirectional"))
    )
    (net (code "42") (name "/LSM_DRDY") (class "Default")
      (node (ref "U1") (pin "9") (pinfunction "DRDY_9") (pintype "bidirectional"))
    )
    (net (code "43") (name "/LSM_WTM_IRQ") (class "Default")
      (node (ref "U1") (pin "5") (pinfunction "INT1_5") (pintype "output"))
      (node (ref "U10") (pin "34") (pinfunction "34.PB13_34") (pintype "bidirectional"))
    )
    (net (code "44") (name "/NETMFAUX1") (class "Default")
      (node (ref "NETMF_AUX") (pin "3") (pinfunction "3_3") (pintype "passive"))
      (node (ref "U11") (pin "33") (pinfunction "PB12_33") (pintype "bidirectional"))
    )
    (net (code "45") (name "/NETMFAUX2") (class "Default")
      (node (ref "NETMF_AUX") (pin "4") (pinfunction "4_4") (pintype "passive"))
      (node (ref "U11") (pin "34") (pinfunction "PB13_34") (pintype "bidirectional"))
    )
    (net (code "46") (name "/NETMF_IRQ") (class "Default")
      (node (ref "U10") (pin "54") (pinfunction "54.PD2_54") (pintype "bidirectional"))
      (node (ref "U11") (pin "15") (pinfunction "PA1_15") (pintype "bidirectional"))
    )
    (net (code "47") (name "/PWM_IN_AUX1") (class "Default")
      (node (ref "RADIO") (pin "5") (pinfunction "5_5") (pintype "passive"))
      (node (ref "U10") (pin "52") (pinfunction "52.PC11_52") (pintype "bidirectional"))
    )
    (net (code "48") (name "/PWM_IN_AUX2") (class "Default")
      (node (ref "RADIO") (pin "6") (pinfunction "6_6") (pintype "passive"))
      (node (ref "U10") (pin "53") (pinfunction "53.PC12_53") (pintype "bidirectional"))
    )
    (net (code "49") (name "/PWM_IN_AUX3") (class "Default")
      (node (ref "RADIO") (pin "7") (pinfunction "7_7") (pintype "passive"))
      (node (ref "U10") (pin "27") (pinfunction "27.PB1_27") (pintype "bidirectional"))
    )
    (net (code "50") (name "/PWM_IN_AUX4") (class "Default")
      (node (ref "RADIO") (pin "8") (pinfunction "8_8") (pintype "passive"))
      (node (ref "U10") (pin "25") (pinfunction "25.PC5_25") (pintype "bidirectional"))
    )
    (net (code "51") (name "/PWM_IN_PITCH") (class "Default")
      (node (ref "RADIO") (pin "1") (pinfunction "1_1") (pintype "passive"))
      (node (ref "U10") (pin "56") (pinfunction "56.PB4_56") (pintype "bidirectional"))
    )
    (net (code "52") (name "/PWM_IN_ROLL") (class "Default")
      (node (ref "RADIO") (pin "2") (pinfunction "2_2") (pintype "passive"))
      (node (ref "U10") (pin "57") (pinfunction "57.PB5_57") (pintype "bidirectional"))
    )
    (net (code "53") (name "/PWM_IN_THRTL") (class "Default")
      (node (ref "RADIO") (pin "3") (pinfunction "3_3") (pintype "passive"))
      (node (ref "U10") (pin "59") (pinfunction "59.PB7_59") (pintype "bidirectional"))
    )
    (net (code "54") (name "/PWM_IN_YAW") (class "Default")
      (node (ref "RADIO") (pin "4") (pinfunction "4_4") (pintype "passive"))
      (node (ref "U10") (pin "58") (pinfunction "58.PB6_58") (pintype "bidirectional"))
    )
    (net (code "55") (name "/PWM_OUT_AUX1") (class "Default")
      (node (ref "AUX-OUT1") (pin "1") (pinfunction "1_1") (pintype "passive"))
      (node (ref "U10") (pin "55") (pinfunction "55.PB3_55") (pintype "bidirectional"))
    )
    (net (code "56") (name "/PWM_OUT_AUX2") (class "Default")
      (node (ref "AUX-OUT2") (pin "1") (pinfunction "1_1") (pintype "passive"))
      (node (ref "U10") (pin "29") (pinfunction "29.PB10_29") (pintype "bidirectional"))
    )
    (net (code "57") (name "/PWM_OUT_FRONT") (class "Default")
      (node (ref "FRONT") (pin "1") (pinfunction "1_1") (pintype "passive"))
      (node (ref "U10") (pin "37") (pinfunction "37.PC6_37") (pintype "bidirectional"))
    )
    (net (code "58") (name "/PWM_OUT_LEFT") (class "Default")
      (node (ref "LEFT") (pin "1") (pinfunction "1_1") (pintype "passive"))
      (node (ref "U10") (pin "38") (pinfunction "38.PC7_38") (pintype "bidirectional"))
    )
    (net (code "59") (name "/PWM_OUT_REAR") (class "Default")
      (node (ref "REAR") (pin "1") (pinfunction "1_1") (pintype "passive"))
      (node (ref "U10") (pin "30") (pinfunction "30.PB11_30") (pintype "bidirectional"))
      (node (ref "U10") (pin "40") (pinfunction "40.PC9_40") (pintype "bidirectional"))
    )
    (net (code "60") (name "/PWM_OUT_RIGHT") (class "Default")
      (node (ref "RIGHT") (pin "1") (pinfunction "1_1") (pintype "passive"))
      (node (ref "U10") (pin "39") (pinfunction "39.PC8_39") (pintype "bidirectional"))
    )
    (net (code "61") (name "/SPI1_NETMF_MISO") (class "Default")
      (node (ref "R22") (pin "1") (pinfunction "1_1") (pintype "passive"))
      (node (ref "U10") (pin "22") (pinfunction "22.PA6_22") (pintype "bidirectional"))
      (node (ref "U11") (pin "56") (pinfunction "PB4_56") (pintype "bidirectional"))
    )
    (net (code "62") (name "/SPI1_NETMF_MOSI") (class "Default")
      (node (ref "R2") (pin "1") (pinfunction "1_1") (pintype "passive"))
      (node (ref "U10") (pin "23") (pinfunction "23.PA7_23") (pintype "bidirectional"))
      (node (ref "U11") (pin "57") (pinfunction "PB5_57") (pintype "bidirectional"))
    )
    (net (code "63") (name "/SPI1_NETMF_SCK") (class "Default")
      (node (ref "U10") (pin "21") (pinfunction "21.PA5_21") (pintype "bidirectional"))
      (node (ref "U11") (pin "55") (pinfunction "PB3_55") (pintype "bidirectional"))
    )
    (net (code "64") (name "/SPI1_NETMF_SS") (class "Default")
      (node (ref "U10") (pin "20") (pinfunction "20.PA4_20") (pintype "bidirectional"))
      (node (ref "U11") (pin "14") (pinfunction "PA0_14") (pintype "bidirectional"))
    )
    (net (code "65") (name "/USART1_GPS_RX") (class "Default")
      (node (ref "U$4") (pin "2") (pinfunction "TXD_2") (pintype "bidirectional"))
      (node (ref "U10") (pin "43") (pinfunction "43.PA10_43") (pintype "bidirectional"))
    )
    (net (code "66") (name "/USART1_GPS_TX") (class "Default")
      (node (ref "DEBUG") (pin "1") (pinfunction "1_1") (pintype "passive"))
      (node (ref "U$4") (pin "1") (pinfunction "RXD_1") (pintype "bidirectional"))
      (node (ref "U10") (pin "42") (pinfunction "42.PA9_42") (pintype "bidirectional"))
    )
    (net (code "67") (name "/USART2_WIFI_CTS") (class "Default")
      (node (ref "U10") (pin "14") (pinfunction "14.PA0_14") (pintype "bidirectional"))
      (node (ref "XBEE") (pin "16") (pinfunction "RTS_16") (pintype "input"))
    )
    (net (code "68") (name "/USART2_WIFI_RTS") (class "Default")
      (node (ref "U10") (pin "15") (pinfunction "15.PA1_15") (pintype "bidirectional"))
      (node (ref "XBEE") (pin "12") (pinfunction "CTS_12") (pintype "output"))
    )
    (net (code "69") (name "/USART2_WIFI_RX") (class "Default")
      (node (ref "U10") (pin "17") (pinfunction "17.PA3_17") (pintype "bidirectional"))
      (node (ref "U11") (pin "38") (pinfunction "PC7_38") (pintype "bidirectional"))
      (node (ref "XBEE") (pin "2") (pinfunction "DOUT_2") (pintype "output"))
    )
    (net (code "70") (name "/USART2_WIFI_TX") (class "Default")
      (node (ref "U10") (pin "16") (pinfunction "16.PA2_16") (pintype "bidirectional"))
      (node (ref "XBEE") (pin "3") (pinfunction "DIN_3") (pintype "input"))
    )
    (net (code "71") (name "/USART4_RX") (class "Default")
      (node (ref "AUX_SER1") (pin "3") (pinfunction "3_3") (pintype "passive"))
      (node (ref "U11") (pin "52") (pinfunction "PC11_52") (pintype "bidirectional"))
    )
    (net (code "72") (name "/USART4_TX") (class "Default")
      (node (ref "AUX_SER1") (pin "2") (pinfunction "2_2") (pintype "passive"))
      (node (ref "U11") (pin "51") (pinfunction "PC10_51") (pintype "bidirectional"))
    )
    (net (code "73") (name "/USB_DM") (class "Default")
      (node (ref "R4") (pin "1") (pinfunction "1_1") (pintype "passive"))
      (node (ref "USB1") (pin "D-") (pinfunction "D-_D-") (pintype "bidirectional"))
    )
    (net (code "74") (name "/USB_DM_IN") (class "Default")
      (node (ref "R4") (pin "2") (pinfunction "2_2") (pintype "passive"))
      (node (ref "SJ1") (pin "2") (pinfunction "2_2") (pintype "passive"))
      (node (ref "SJ3") (pin "1") (pinfunction "1_1") (pintype "passive"))
    )
    (net (code "75") (name "/USB_DP") (class "Default")
      (node (ref "R5") (pin "1") (pinfunction "1_1") (pintype "passive"))
      (node (ref "USB1") (pin "D+") (pinfunction "D+_D+") (pintype "bidirectional"))
    )
    (net (code "76") (name "/USB_DP_IN") (class "Default")
      (node (ref "R5") (pin "2") (pinfunction "2_2") (pintype "passive"))
      (node (ref "SJ2") (pin "2") (pinfunction "2_2") (pintype "passive"))
      (node (ref "SJ4") (pin "1") (pinfunction "1_1") (pintype "passive"))
    )
    (net (code "77") (name "/VBAT") (class "Default")
      (node (ref "U11") (pin "1") (pinfunction "VBAT_1") (pintype "bidirectional"))
    )
    (net (code "78") (name "/VIN") (class "Default")
      (node (ref "F2") (pin "P$2") (pinfunction "P$2_P$2") (pintype "bidirectional"))
      (node (ref "U12") (pin "3") (pinfunction "VIN_3") (pintype "bidirectional"))
    )
    (net (code "79") (name "/WIFI_RESET") (class "Default")
      (node (ref "U10") (pin "26") (pinfunction "26.PB0_26") (pintype "bidirectional"))
      (node (ref "XBEE") (pin "5") (pinfunction "RESET_5") (pintype "input"))
    )
    (net (code "80") (name "/WIFLY_AP") (class "Default")
      (node (ref "AP") (pin "2") (pinfunction "2_2") (pintype "passive"))
      (node (ref "XBEE") (pin "9") (pinfunction "DTR_9") (pintype "bidirectional"))
    )
    (net (code "81") (name "GND") (class "Default")
      (node (ref "AUX-OUT1") (pin "3") (pinfunction "3_3") (pintype "passive"))
      (node (ref "AUX-OUT2") (pin "3") (pinfunction "3_3") (pintype "passive"))
      (node (ref "AUX_SER1") (pin "4") (pinfunction "4_4") (pintype "passive"))
      (node (ref "C1") (pin "2") (pinfunction "2_2") (pintype "passive"))
      (node (ref "C10") (pin "-") (pinfunction "-_-") (pintype "passive"))
      (node (ref "C11") (pin "1") (pinfunction "1_1") (pintype "passive"))
      (node (ref "C12") (pin "1") (pinfunction "1_1") (pintype "passive"))
      (node (ref "C13") (pin "1") (pinfunction "1_1") (pintype "passive"))
      (node (ref "C14") (pin "1") (pinfunction "1_1") (pintype "passive"))
      (node (ref "C16") (pin "1") (pinfunction "1_1") (pintype "passive"))
      (node (ref "C17") (pin "1") (pinfunction "1_1") (pintype "passive"))
      (node (ref "C18") (pin "1") (pinfunction "1_1") (pintype "passive"))
      (node (ref "C19") (pin "1") (pinfunction "1_1") (pintype "passive"))
      (node (ref "C2") (pin "2") (pinfunction "2_2") (pintype "passive"))
      (node (ref "C20") (pin "1") (pinfunction "1_1") (pintype "passive"))
      (node (ref "C21") (pin "1") (pinfunction "1_1") (pintype "passive"))
      (node (ref "C22") (pin "1") (pinfunction "1_1") (pintype "passive"))
      (node (ref "C23") (pin "1") (pinfunction "1_1") (pintype "passive"))
      (node (ref "C24") (pin "1") (pinfunction "1_1") (pintype "passive"))
      (node (ref "C25") (pin "-") (pinfunction "-_-") (pintype "passive"))
      (node (ref "C26") (pin "1") (pinfunction "1_1") (pintype "passive"))
      (node (ref "C27") (pin "2") (pinfunction "2_2") (pintype "passive"))
      (node (ref "C3") (pin "2") (pinfunction "2_2") (pintype "passive"))
      (node (ref "C4") (pin "2") (pinfunction "2_2") (pintype "passive"))
      (node (ref "C40") (pin "2") (pinfunction "2_2") (pintype "passive"))
      (node (ref "C41") (pin "2") (pinfunction "2_2") (pintype "passive"))
      (node (ref "C44") (pin "1") (pinfunction "1_1") (pintype "passive"))
      (node (ref "C45") (pin "1") (pinfunction "1_1") (pintype "passive"))
      (node (ref "C46") (pin "2") (pinfunction "2_2") (pintype "passive"))
      (node (ref "C47") (pin "2") (pinfunction "2_2") (pintype "passive"))
      (node (ref "C48") (pin "1") (pinfunction "1_1") (pintype "passive"))
      (node (ref "C6") (pin "2") (pinfunction "2_2") (pintype "passive"))
      (node (ref "C7") (pin "2") (pinfunction "2_2") (pintype "passive"))
      (node (ref "C8") (pin "2") (pinfunction "2_2") (pintype "passive"))
      (node (ref "C9") (pin "2") (pinfunction "2_2") (pintype "passive"))
      (node (ref "CONSOLE") (pin "4") (pinfunction "4_4") (pintype "passive"))
      (node (ref "DEBUG") (pin "2") (pinfunction "2_2") (pintype "passive"))
      (node (ref "FRONT") (pin "3") (pinfunction "3_3") (pintype "passive"))
      (node (ref "GO_BUS") (pin "10") (pinfunction "GND_10") (pintype "power_in"))
      (node (ref "JP1") (pin "2") (pinfunction "2_2") (pintype "passive"))
      (node (ref "LEFT") (pin "3") (pinfunction "3_3") (pintype "passive"))
      (node (ref "LIPO") (pin "4") (pinfunction "4_4") (pintype "passive"))
      (node (ref "NETMF_AUX") (pin "1") (pinfunction "1_1") (pintype "passive"))
      (node (ref "R10") (pin "1") (pinfunction "1_1") (pintype "passive"))
      (node (ref "R12") (pin "1") (pinfunction "1_1") (pintype "passive"))
      (node (ref "R19") (pin "1") (pinfunction "1_1") (pintype "passive"))
      (node (ref "R23") (pin "1") (pinfunction "1_1") (pintype "passive"))
      (node (ref "R8") (pin "1") (pinfunction "1_1") (pintype "passive"))
      (node (ref "REAR") (pin "3") (pinfunction "3_3") (pintype "passive"))
      (node (ref "RIGHT") (pin "3") (pinfunction "3_3") (pintype "passive"))
      (node (ref "SONAR") (pin "1") (pinfunction "1_1") (pintype "passive"))
      (node (ref "SWD1") (pin "3") (pinfunction "P$3_3") (pintype "bidirectional"))
      (node (ref "SWD2") (pin "3") (pinfunction "P$3_3") (pintype "bidirectional"))
      (node (ref "U$12") (pin "2") (pinfunction "PS_2") (pintype "bidirectional"))
      (node (ref "U$12") (pin "3") (pinfunction "GND_3") (pintype "bidirectional"))
      (node (ref "U$4") (pin "3") (pinfunction "GND_3") (pintype "bidirectional"))
      (node (ref "U1") (pin "10") (pinfunction "GND2_10") (pintype "power_in"))
      (node (ref "U1") (pin "11") (pinfunction "GND3_11") (pintype "power_in"))
      (node (ref "U1") (pin "7") (pinfunction "GND_7") (pintype "power_in"))
      (node (ref "U1") (pin "8") (pinfunction "GND1_8") (pintype "power_in"))
      (node (ref "U10") (pin "12") (pinfunction "12.VSSA_12") (pintype "passive"))
      (node (ref "U10") (pin "18") (pinfunction "18.PF4_18") (pintype "bidirectional"))
      (node (ref "U10") (pin "63") (pinfunction "63.VSS_2_63") (pintype "passive"))
      (node (ref "U11") (pin "12") (pinfunction "VSSA_12") (pintype "bidirectional"))
      (node (ref "U11") (pin "18") (pinfunction "VSS1_18") (pintype "bidirectional"))
      (node (ref "U11") (pin "63") (pinfunction "VSS2_63") (pintype "bidirectional"))
      (node (ref "U12") (pin "1") (pinfunction "GND_1") (pintype "bidirectional"))
      (node (ref "U13") (pin "1") (pinfunction "GND_1") (pintype "bidirectional"))
      (node (ref "U2") (pin "10") (pinfunction "RSVDG_10") (pintype "bidirectional"))
      (node (ref "U2") (pin "11") (pinfunction "RSDVG_11") (pintype "bidirectional"))
      (node (ref "U2") (pin "12") (pinfunction "RSVDG_12") (pintype "bidirectional"))
      (node (ref "U2") (pin "13") (pinfunction "GND_13") (pintype "bidirectional"))
      (node (ref "U2") (pin "4") (pinfunction "SDO_4") (pintype "bidirectional"))
      (node (ref "U2") (pin "8") (pinfunction "RSVDG_8") (pintype "bidirectional"))
      (node (ref "U2") (pin "9") (pinfunction "RSVDG_9") (pintype "bidirectional"))
      (node (ref "U3") (pin "1") (pinfunction "CLKIN_1") (pintype "bidirectional"))
      (node (ref "U3") (pin "11") (pinfunction "RESV-G_11") (pintype "bidirectional"))
      (node (ref "U3") (pin "18") (pinfunction "GND_18") (pintype "bidirectional"))
      (node (ref "U3") (pin "9") (pinfunction "AD0_9") (pintype "bidirectional"))
      (node (ref "U4") (pin "12") (pinfunction "SDO_12") (pintype "bidirectional"))
      (node (ref "U4") (pin "2") (pinfunction "GND_2") (pintype "bidirectional"))
      (node (ref "U4") (pin "4") (pinfunction "GND_4") (pintype "bidirectional"))
      (node (ref "U4") (pin "5") (pinfunction "GND_5") (pintype "bidirectional"))
      (node (ref "U5") (pin "1") (pinfunction "GND_1") (pintype "power_in"))
      (node (ref "U7") (pin "1") (pinfunction "A0_1") (pintype "input"))
      (node (ref "U7") (pin "2") (pinfunction "A1_2") (pintype "input"))
      (node (ref "U7") (pin "3") (pinfunction "A2_3") (pintype "input"))
      (node (ref "U7") (pin "4") (pinfunction "GND_4") (pintype "power_in"))
      (node (ref "U7") (pin "7") (pinfunction "WP_7") (pintype "input"))
      (node (ref "U8") (pin "11") (pinfunction "GND_11") (pintype "bidirectional"))
      (node (ref "U8") (pin "9") (pinfunction "GND_9") (pintype "bidirectional"))
      (node (ref "USB1") (pin "GND") (pinfunction "GND_GND") (pintype "bidirectional"))
      (node (ref "XBEE") (pin "10") (pinfunction "GND_10") (pintype "power_in"))
    )
    (net (code "82") (name "Net-(ARMED-PadC)") (class "Default")
      (node (ref "ARMED") (pin "C") (pinfunction "C_C") (pintype "passive"))
      (node (ref "R20") (pin "2") (pinfunction "2_2") (pintype "passive"))
    )
    (net (code "83") (name "Net-(C7-Pad1)") (class "Default")
      (node (ref "C7") (pin "1") (pinfunction "1_1") (pintype "passive"))
      (node (ref "R3") (pin "2") (pinfunction "2_2") (pintype "passive"))
      (node (ref "X1") (pin "P$2") (pinfunction "P$2_P$2") (pintype "passive"))
    )
    (net (code "84") (name "Net-(C45-Pad2)") (class "Default")
      (node (ref "C45") (pin "2") (pinfunction "2_2") (pintype "passive"))
      (node (ref "R1") (pin "1") (pinfunction "1_1") (pintype "passive"))
      (node (ref "X2") (pin "P$2") (pinfunction "P$2_P$2") (pintype "passive"))
    )
    (net (code "85") (name "Net-(F2-PadP$1)") (class "Default")
      (node (ref "F2") (pin "P$1") (pinfunction "P$1_P$1") (pintype "bidirectional"))
      (node (ref "LIPO") (pin "1") (pinfunction "1_1") (pintype "passive"))
      (node (ref "R7") (pin "2") (pinfunction "2_2") (pintype "passive"))
    )
    (net (code "86") (name "Net-(GPS_LOCK-PadC)") (class "Default")
      (node (ref "GPS_LOCK") (pin "C") (pinfunction "C_C") (pintype "passive"))
      (node (ref "R21") (pin "2") (pinfunction "2_2") (pintype "passive"))
    )
    (net (code "87") (name "Net-(LIPO-Pad2)") (class "Default")
      (node (ref "LIPO") (pin "2") (pinfunction "2_2") (pintype "passive"))
      (node (ref "R9") (pin "2") (pinfunction "2_2") (pintype "passive"))
    )
    (net (code "88") (name "Net-(LIPO-Pad3)") (class "Default")
      (node (ref "LIPO") (pin "3") (pinfunction "3_3") (pintype "passive"))
      (node (ref "R11") (pin "2") (pinfunction "2_2") (pintype "passive"))
    )
    (net (code "89") (name "Net-(POWER-PadC)") (class "Default")
      (node (ref "POWER") (pin "C") (pinfunction "C_C") (pintype "passive"))
      (node (ref "R19") (pin "2") (pinfunction "2_2") (pintype "passive"))
    )
    (net (code "90") (name "Net-(R15-Pad2)") (class "Default")
      (node (ref "R15") (pin "2") (pinfunction "2_2") (pintype "passive"))
      (node (ref "SNSR_ONLINE") (pin "C") (pinfunction "C_C") (pintype "passive"))
    )
    (net (code "91") (name "Net-(R16-Pad2)") (class "Default")
      (node (ref "R16") (pin "2") (pinfunction "2_2") (pintype "passive"))
      (node (ref "SNSR_FAIL") (pin "C") (pinfunction "C_C") (pintype "passive"))
    )
    (net (code "92") (name "Net-(R17-Pad2)") (class "Default")
      (node (ref "R17") (pin "2") (pinfunction "2_2") (pintype "passive"))
      (node (ref "WIFI") (pin "C") (pinfunction "C_C") (pintype "passive"))
    )
    (net (code "93") (name "Net-(R18-Pad2)") (class "Default")
      (node (ref "R18") (pin "2") (pinfunction "2_2") (pintype "passive"))
      (node (ref "RC") (pin "C") (pinfunction "C_C") (pintype "passive"))
    )
    (net (code "94") (name "Net-(U1-C1)") (class "Default")
      (node (ref "C16") (pin "2") (pinfunction "2_2") (pintype "passive"))
      (node (ref "U1") (pin "6") (pinfunction "C1_6") (pintype "bidirectional"))
    )
    (net (code "95") (name "Net-(U1-SETC)") (class "Default")
      (node (ref "C15") (pin "2") (pinfunction "2_2") (pintype "passive"))
      (node (ref "U1") (pin "13") (pinfunction "SETC_13") (pintype "bidirectional"))
    )
    (net (code "96") (name "Net-(U1-SETP)") (class "Default")
      (node (ref "C15") (pin "1") (pinfunction "1_1") (pintype "passive"))
      (node (ref "U1") (pin "12") (pinfunction "SETP_12") (pintype "bidirectional"))
    )
    (net (code "97") (name "Net-(U2-PLL)") (class "Default")
      (node (ref "C22") (pin "2") (pinfunction "2_2") (pintype "passive"))
      (node (ref "U2") (pin "14") (pinfunction "PLL_14") (pintype "bidirectional"))
    )
    (net (code "98") (name "Net-(U3-CPOUT)") (class "Default")
      (node (ref "C12") (pin "2") (pinfunction "2_2") (pintype "passive"))
      (node (ref "U3") (pin "20") (pinfunction "CPOUT_20") (pintype "bidirectional"))
    )
    (net (code "99") (name "Net-(U3-REGOUT)") (class "Default")
      (node (ref "C13") (pin "2") (pinfunction "2_2") (pintype "passive"))
      (node (ref "U3") (pin "10") (pinfunction "REGOUT_10") (pintype "bidirectional"))
    )
    (net (code "100") (name "Net-(U8-C1)") (class "Default")
      (node (ref "C11") (pin "2") (pinfunction "2_2") (pintype "passive"))
      (node (ref "U8") (pin "10") (pinfunction "C1_10") (pintype "bidirectional"))
    )
    (net (code "101") (name "Net-(U8-SETC)") (class "Default")
      (node (ref "C5") (pin "1") (pinfunction "1_1") (pintype "passive"))
      (node (ref "U8") (pin "12") (pinfunction "SETC_12") (pintype "bidirectional"))
    )
    (net (code "102") (name "Net-(U8-SETP)") (class "Default")
      (node (ref "C5") (pin "2") (pinfunction "2_2") (pintype "passive"))
      (node (ref "U8") (pin "8") (pinfunction "SETP_8") (pintype "bidirectional"))
    )
    (net (code "103") (name "Net-(U10-5.PF0-OSC_IN)") (class "Default")
      (node (ref "C44") (pin "2") (pinfunction "2_2") (pintype "passive"))
      (node (ref "U10") (pin "5") (pinfunction "5.PF0-OSC_IN_5") (pintype "bidirectional"))
      (node (ref "X2") (pin "P$1") (pinfunction "P$1_P$1") (pintype "passive"))
    )
    (net (code "104") (name "Net-(U10-6.PF1-OSC_OUT)") (class "Default")
      (node (ref "R1") (pin "2") (pinfunction "2_2") (pintype "passive"))
      (node (ref "U10") (pin "6") (pinfunction "6.PF1-OSC_OUT_6") (pintype "bidirectional"))
    )
    (net (code "105") (name "Net-(U10-31.VSS_1)") (class "Default")
      (node (ref "C26") (pin "2") (pinfunction "2_2") (pintype "passive"))
      (node (ref "U10") (pin "31") (pinfunction "31.VSS_1_31") (pintype "passive"))
    )
    (net (code "106") (name "Net-(U10-44.PA11)") (class "Default")
      (node (ref "SJ1") (pin "1") (pinfunction "1_1") (pintype "passive"))
      (node (ref "U10") (pin "44") (pinfunction "44.PA11_44") (pintype "bidirectional"))
    )
    (net (code "107") (name "Net-(U10-45.PA12)") (class "Default")
      (node (ref "SJ2") (pin "1") (pinfunction "1_1") (pintype "passive"))
      (node (ref "U10") (pin "45") (pinfunction "45.PA12_45") (pintype "bidirectional"))
    )
    (net (code "108") (name "Net-(U10-47.PF6)") (class "Default")
      (node (ref "C27") (pin "1") (pinfunction "1_1") (pintype "passive"))
      (node (ref "U10") (pin "47") (pinfunction "47.PF6_47") (pintype "passive"))
    )
    (net (code "109") (name "Net-(U10-60.BOOT0)") (class "Default")
      (node (ref "R23") (pin "2") (pinfunction "2_2") (pintype "passive"))
      (node (ref "TP0") (pin "TP") (pinfunction "TP_TP") (pintype "input"))
      (node (ref "U10") (pin "60") (pinfunction "60.BOOT0_60") (pintype "bidirectional"))
    )
    (net (code "110") (name "Net-(U11-BOOT0)") (class "Default")
      (node (ref "R6") (pin "1") (pinfunction "1_1") (pintype "passive"))
      (node (ref "TP1") (pin "TP") (pinfunction "TP_TP") (pintype "input"))
      (node (ref "U11") (pin "60") (pinfunction "BOOT0_60") (pintype "bidirectional"))
    )
    (net (code "111") (name "Net-(U11-PA11)") (class "Default")
      (node (ref "SJ3") (pin "2") (pinfunction "2_2") (pintype "passive"))
      (node (ref "U11") (pin "44") (pinfunction "PA11_44") (pintype "bidirectional"))
    )
    (net (code "112") (name "Net-(U11-PA12)") (class "Default")
      (node (ref "SJ4") (pin "2") (pinfunction "2_2") (pintype "passive"))
      (node (ref "U11") (pin "45") (pinfunction "PA12_45") (pintype "bidirectional"))
    )
    (net (code "113") (name "Net-(U11-PH0)") (class "Default")
      (node (ref "C6") (pin "1") (pinfunction "1_1") (pintype "passive"))
      (node (ref "U11") (pin "5") (pinfunction "PH0_5") (pintype "bidirectional"))
      (node (ref "X1") (pin "P$1") (pinfunction "P$1_P$1") (pintype "passive"))
    )
    (net (code "114") (name "Net-(U11-PH1)") (class "Default")
      (node (ref "R3") (pin "1") (pinfunction "1_1") (pintype "passive"))
      (node (ref "U11") (pin "6") (pinfunction "PH1_6") (pintype "bidirectional"))
    )
    (net (code "115") (name "Net-(U11-VCAP_1)") (class "Default")
      (node (ref "C8") (pin "1") (pinfunction "1_1") (pintype "passive"))
      (node (ref "U11") (pin "31") (pinfunction "VCAP_1_31") (pintype "bidirectional"))
    )
    (net (code "116") (name "Net-(U11-VCAP_2)") (class "Default")
      (node (ref "C9") (pin "1") (pinfunction "1_1") (pintype "passive"))
      (node (ref "U11") (pin "47") (pinfunction "VCAP_2_47") (pintype "bidirectional"))
    )
    (net (code "117") (name "unconnected-(FRONT-Pad2)") (class "Default")
      (node (ref "FRONT") (pin "2") (pinfunction "2_2") (pintype "passive"))
    )
    (net (code "118") (name "unconnected-(LEFT-Pad2)") (class "Default")
      (node (ref "LEFT") (pin "2") (pinfunction "2_2") (pintype "passive"))
    )
    (net (code "119") (name "unconnected-(REAR-Pad2)") (class "Default")
      (node (ref "REAR") (pin "2") (pinfunction "2_2") (pintype "passive"))
    )
    (net (code "120") (name "unconnected-(RIGHT-Pad2)") (class "Default")
      (node (ref "RIGHT") (pin "2") (pinfunction "2_2") (pintype "passive"))
    )
    (net (code "121") (name "unconnected-(U$12-CSB2-Pad5)") (class "Default")
      (node (ref "U$12") (pin "5") (pinfunction "CSB2_5") (pintype "bidirectional"))
    )
    (net (code "122") (name "unconnected-(U$12-SDO-Pad6)") (class "Default")
      (node (ref "U$12") (pin "6") (pinfunction "SDO_6") (pintype "bidirectional"))
    )
    (net (code "123") (name "unconnected-(U1-INT2-Pad4)") (class "Default")
      (node (ref "U1") (pin "4") (pinfunction "INT2_4") (pintype "output"))
    )
    (net (code "124") (name "unconnected-(U2-INT1-Pad7)") (class "Default")
      (node (ref "U2") (pin "7") (pinfunction "INT1_7") (pintype "bidirectional"))
    )
    (net (code "125") (name "unconnected-(U4-INT2-Pad9)") (class "Default")
      (node (ref "U4") (pin "9") (pinfunction "INT2_9") (pintype "bidirectional"))
    )
    (net (code "126") (name "unconnected-(U4-NC-Pad3)") (class "Default")
      (node (ref "U4") (pin "3") (pinfunction "NC_3") (pintype "bidirectional"))
    )
    (net (code "127") (name "unconnected-(U4-NC-Pad10)") (class "Default")
      (node (ref "U4") (pin "10") (pinfunction "NC_10") (pintype "bidirectional"))
    )
    (net (code "128") (name "unconnected-(U4-NC-Pad11)") (class "Default")
      (node (ref "U4") (pin "11") (pinfunction "NC_11") (pintype "bidirectional"))
    )
    (net (code "129") (name "unconnected-(U5-NC-Pad5)") (class "Default")
      (node (ref "U5") (pin "5") (pinfunction "NC_5") (pintype "bidirectional"))
    )
    (net (code "130") (name "unconnected-(U8-NC-Pad3)") (class "Default")
      (node (ref "U8") (pin "3") (pinfunction "NC_3") (pintype "bidirectional"))
    )
    (net (code "131") (name "unconnected-(U8-NC-Pad5)") (class "Default")
      (node (ref "U8") (pin "5") (pinfunction "NC_5") (pintype "bidirectional"))
    )
    (net (code "132") (name "unconnected-(U8-NC-Pad6)") (class "Default")
      (node (ref "U8") (pin "6") (pinfunction "NC_6") (pintype "bidirectional"))
    )
    (net (code "133") (name "unconnected-(U8-NC-Pad7)") (class "Default")
      (node (ref "U8") (pin "7") (pinfunction "NC_7") (pintype "bidirectional"))
    )
    (net (code "134") (name "unconnected-(U8-NC-Pad14)") (class "Default")
      (node (ref "U8") (pin "14") (pinfunction "NC_14") (pintype "bidirectional"))
    )
    (net (code "135") (name "unconnected-(U10-4.PC15-OSC32_OUT-Pad4)") (class "Default")
      (node (ref "U10") (pin "4") (pinfunction "4.PC15-OSC32_OUT_4") (pintype "bidirectional"))
    )
    (net (code "136") (name "unconnected-(U11-PA2-Pad16)") (class "Default")
      (node (ref "U11") (pin "16") (pinfunction "PA2_16") (pintype "bidirectional"))
    )
    (net (code "137") (name "unconnected-(U11-PA3-Pad17)") (class "Default")
      (node (ref "U11") (pin "17") (pinfunction "PA3_17") (pintype "bidirectional"))
    )
    (net (code "138") (name "unconnected-(U11-PA4-Pad20)") (class "Default")
      (node (ref "U11") (pin "20") (pinfunction "PA4_20") (pintype "bidirectional"))
    )
    (net (code "139") (name "unconnected-(U11-PA9-Pad42)") (class "Default")
      (node (ref "U11") (pin "42") (pinfunction "PA9_42") (pintype "bidirectional"))
    )
    (net (code "140") (name "unconnected-(U11-PA10-Pad43)") (class "Default")
      (node (ref "U11") (pin "43") (pinfunction "PA10_43") (pintype "bidirectional"))
    )
    (net (code "141") (name "unconnected-(U11-PA15-Pad50)") (class "Default")
      (node (ref "U11") (pin "50") (pinfunction "PA15_50") (pintype "bidirectional"))
    )
    (net (code "142") (name "unconnected-(U11-PB0-Pad26)") (class "Default")
      (node (ref "U11") (pin "26") (pinfunction "PB0_26") (pintype "bidirectional"))
    )
    (net (code "143") (name "unconnected-(U11-PB1-Pad27)") (class "Default")
      (node (ref "U11") (pin "27") (pinfunction "PB1_27") (pintype "bidirectional"))
    )
    (net (code "144") (name "unconnected-(U11-PB2-Pad28)") (class "Default")
      (node (ref "U11") (pin "28") (pinfunction "PB2_28") (pintype "bidirectional"))
    )
    (net (code "145") (name "unconnected-(U11-PB8-Pad61)") (class "Default")
      (node (ref "U11") (pin "61") (pinfunction "PB8_61") (pintype "bidirectional"))
    )
    (net (code "146") (name "unconnected-(U11-PB10-Pad29)") (class "Default")
      (node (ref "U11") (pin "29") (pinfunction "PB10_29") (pintype "bidirectional"))
    )
    (net (code "147") (name "unconnected-(U11-PB11-Pad30)") (class "Default")
      (node (ref "U11") (pin "30") (pinfunction "PB11_30") (pintype "bidirectional"))
    )
    (net (code "148") (name "unconnected-(U11-PB14-Pad35)") (class "Default")
      (node (ref "U11") (pin "35") (pinfunction "PB14_35") (pintype "bidirectional"))
    )
    (net (code "149") (name "unconnected-(U11-PB15-Pad36)") (class "Default")
      (node (ref "U11") (pin "36") (pinfunction "PB15_36") (pintype "bidirectional"))
    )
    (net (code "150") (name "unconnected-(U11-PC0-Pad8)") (class "Default")
      (node (ref "U11") (pin "8") (pinfunction "PC0_8") (pintype "bidirectional"))
    )
    (net (code "151") (name "unconnected-(U11-PC1-Pad9)") (class "Default")
      (node (ref "U11") (pin "9") (pinfunction "PC1_9") (pintype "bidirectional"))
    )
    (net (code "152") (name "unconnected-(U11-PC2-Pad10)") (class "Default")
      (node (ref "U11") (pin "10") (pinfunction "PC2_10") (pintype "bidirectional"))
    )
    (net (code "153") (name "unconnected-(U11-PC3-Pad11)") (class "Default")
      (node (ref "U11") (pin "11") (pinfunction "PC3_11") (pintype "bidirectional"))
    )
    (net (code "154") (name "unconnected-(U11-PC4-Pad24)") (class "Default")
      (node (ref "U11") (pin "24") (pinfunction "PC4_24") (pintype "bidirectional"))
    )
    (net (code "155") (name "unconnected-(U11-PC5-Pad25)") (class "Default")
      (node (ref "U11") (pin "25") (pinfunction "PC5_25") (pintype "bidirectional"))
    )
    (net (code "156") (name "unconnected-(U11-PC6-Pad37)") (class "Default")
      (node (ref "U11") (pin "37") (pinfunction "PC6_37") (pintype "bidirectional"))
    )
    (net (code "157") (name "unconnected-(U11-PC8-Pad39)") (class "Default")
      (node (ref "U11") (pin "39") (pinfunction "PC8_39") (pintype "bidirectional"))
    )
    (net (code "158") (name "unconnected-(U11-PC12-Pad53)") (class "Default")
      (node (ref "U11") (pin "53") (pinfunction "PC12_53") (pintype "bidirectional"))
    )
    (net (code "159") (name "unconnected-(U11-PC14-Pad3)") (class "Default")
      (node (ref "U11") (pin "3") (pinfunction "PC14_3") (pintype "bidirectional"))
    )
    (net (code "160") (name "unconnected-(U11-PC15-Pad4)") (class "Default")
      (node (ref "U11") (pin "4") (pinfunction "PC15_4") (pintype "bidirectional"))
    )
    (net (code "161") (name "unconnected-(U11-PD2-Pad54)") (class "Default")
      (node (ref "U11") (pin "54") (pinfunction "PD2_54") (pintype "bidirectional"))
    )
    (net (code "162") (name "unconnected-(XBEE-DIO0-Pad20)") (class "Default")
      (node (ref "XBEE") (pin "20") (pinfunction "DIO0_20") (pintype "bidirectional"))
    )
    (net (code "163") (name "unconnected-(XBEE-DIO1-Pad19)") (class "Default")
      (node (ref "XBEE") (pin "19") (pinfunction "DIO1_19") (pintype "bidirectional"))
    )
    (net (code "164") (name "unconnected-(XBEE-DIO2-Pad18)") (class "Default")
      (node (ref "XBEE") (pin "18") (pinfunction "DIO2_18") (pintype "bidirectional"))
    )
    (net (code "165") (name "unconnected-(XBEE-DIO3-Pad17)") (class "Default")
      (node (ref "XBEE") (pin "17") (pinfunction "DIO3_17") (pintype "bidirectional"))
    )
    (net (code "166") (name "unconnected-(XBEE-DIO4-Pad11)") (class "Default")
      (node (ref "XBEE") (pin "11") (pinfunction "DIO4_11") (pintype "bidirectional"))
    )
    (net (code "167") (name "unconnected-(XBEE-DIO5-Pad15)") (class "Default")
      (node (ref "XBEE") (pin "15") (pinfunction "DIO5_15") (pintype "bidirectional"))
    )
    (net (code "168") (name "unconnected-(XBEE-DIO9-Pad13)") (class "Default")
      (node (ref "XBEE") (pin "13") (pinfunction "DIO9_13") (pintype "bidirectional"))
    )
    (net (code "169") (name "unconnected-(XBEE-DIO11-Pad7)") (class "Default")
      (node (ref "XBEE") (pin "7") (pinfunction "DIO11_7") (pintype "bidirectional"))
    )
    (net (code "170") (name "unconnected-(XBEE-DIO12-Pad4)") (class "Default")
      (node (ref "XBEE") (pin "4") (pinfunction "DIO12_4") (pintype "bidirectional"))
    )
    (net (code "171") (name "unconnected-(XBEE-RES-Pad8)") (class "Default")
      (node (ref "XBEE") (pin "8") (pinfunction "RES_8") (pintype "bidirectional"))
    )
    (net (code "172") (name "unconnected-(XBEE-RSSI-Pad6)") (class "Default")
      (node (ref "XBEE") (pin "6") (pinfunction "RSSI_6") (pintype "bidirectional"))
    )
  )
)
